# Pianoshield.net
KiCad netlist of a schematic drawn in Altium Designer
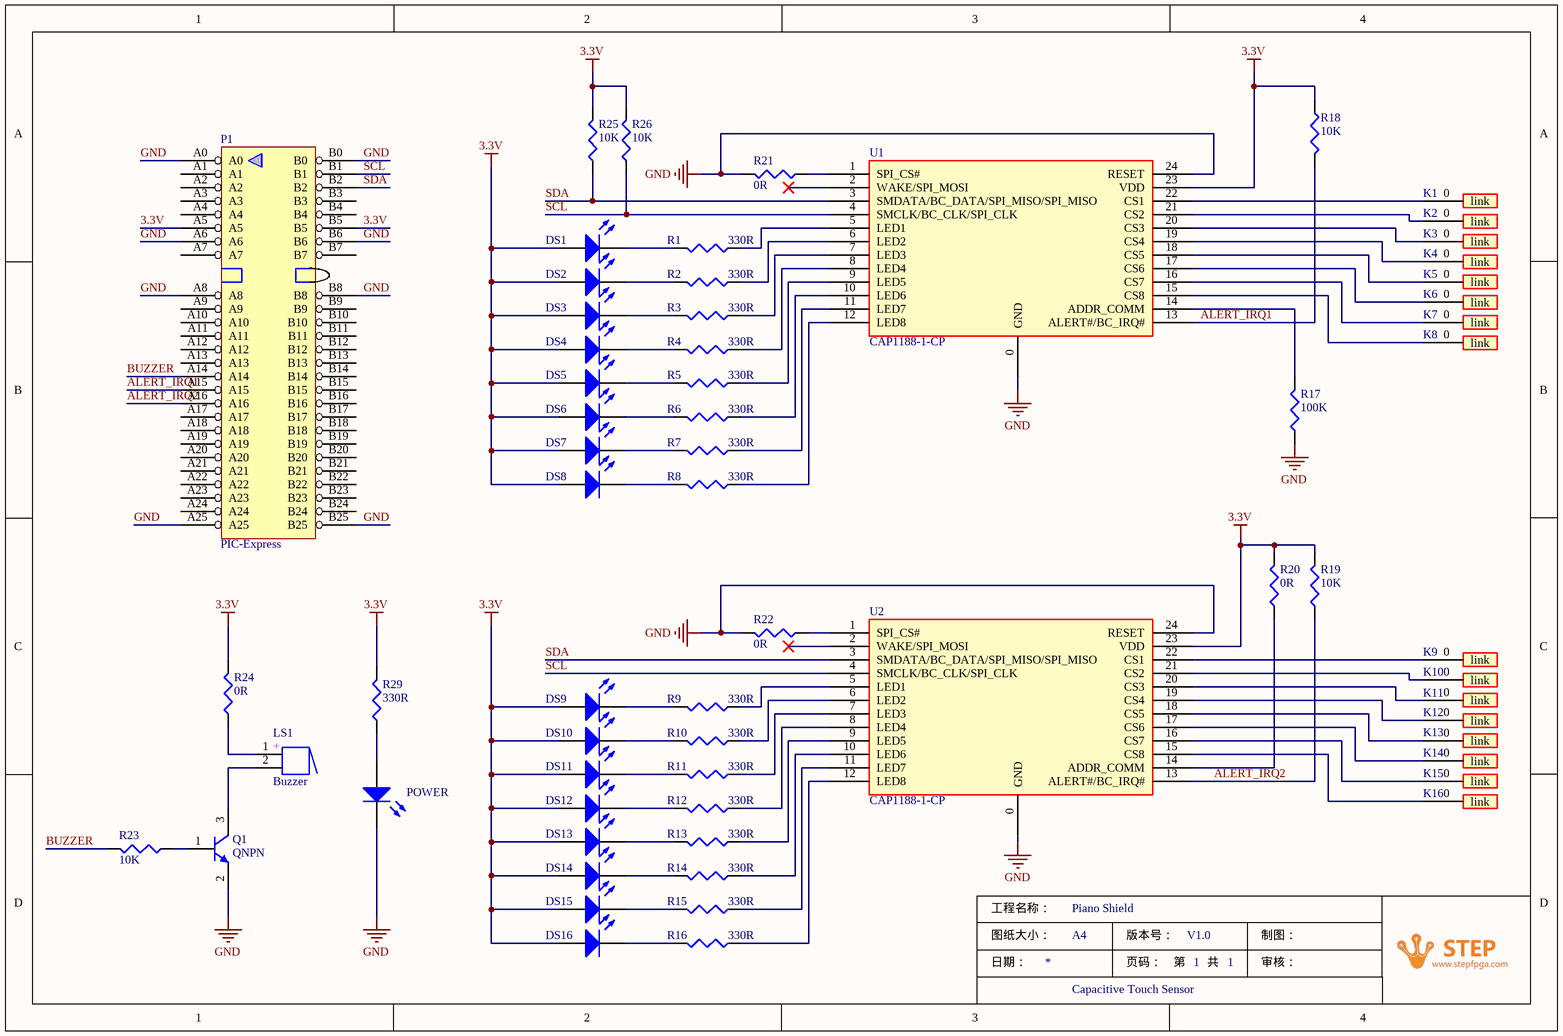
[diagram p0: Pianoshield.SchDoc]

(export (version "E")
  (design (tool "Eeschema 10.0.6"))
  (components
    (comp (ref "DS1")
      (value "Blue")
      (footprint "LED0603")
      (description "贴片LED，0603")
      (fields (field (name "PUBLISHER") "Altium Limited"))
      (libsource (lib "战舰STM32开发板底板封装库") (part "LED2"))
    )
    (comp (ref "DS2")
      (value "Blue")
      (footprint "LED0603")
      (description "贴片LED，0603")
      (fields (field (name "PUBLISHER") "Altium Limited"))
      (libsource (lib "战舰STM32开发板底板封装库") (part "LED2"))
    )
    (comp (ref "DS3")
      (value "Blue")
      (footprint "LED0603")
      (description "贴片LED，0603")
      (fields (field (name "PUBLISHER") "Altium Limited"))
      (libsource (lib "战舰STM32开发板底板封装库") (part "LED2"))
    )
    (comp (ref "DS4")
      (value "Blue")
      (footprint "LED0603")
      (description "贴片LED，0603")
      (fields (field (name "PUBLISHER") "Altium Limited"))
      (libsource (lib "战舰STM32开发板底板封装库") (part "LED2"))
    )
    (comp (ref "DS5")
      (value "Blue")
      (footprint "LED0603")
      (description "贴片LED，0603")
      (fields (field (name "PUBLISHER") "Altium Limited"))
      (libsource (lib "战舰STM32开发板底板封装库") (part "LED2"))
    )
    (comp (ref "DS6")
      (value "Blue")
      (footprint "LED0603")
      (description "贴片LED，0603")
      (fields (field (name "PUBLISHER") "Altium Limited"))
      (libsource (lib "战舰STM32开发板底板封装库") (part "LED2"))
    )
    (comp (ref "DS7")
      (value "Blue")
      (footprint "LED0603")
      (description "贴片LED，0603")
      (fields (field (name "PUBLISHER") "Altium Limited"))
      (libsource (lib "战舰STM32开发板底板封装库") (part "LED2"))
    )
    (comp (ref "DS8")
      (value "Blue")
      (footprint "LED0603")
      (description "贴片LED，0603")
      (fields (field (name "PUBLISHER") "Altium Limited"))
      (libsource (lib "战舰STM32开发板底板封装库") (part "LED2"))
    )
    (comp (ref "DS9")
      (value "Blue")
      (footprint "LED0603")
      (description "贴片LED，0603")
      (fields (field (name "PUBLISHER") "Altium Limited"))
      (libsource (lib "战舰STM32开发板底板封装库") (part "LED2"))
    )
    (comp (ref "DS10")
      (value "Blue")
      (footprint "LED0603")
      (description "贴片LED，0603")
      (fields (field (name "PUBLISHER") "Altium Limited"))
      (libsource (lib "战舰STM32开发板底板封装库") (part "LED2"))
    )
    (comp (ref "DS11")
      (value "Blue")
      (footprint "LED0603")
      (description "贴片LED，0603")
      (fields (field (name "PUBLISHER") "Altium Limited"))
      (libsource (lib "战舰STM32开发板底板封装库") (part "LED2"))
    )
    (comp (ref "DS12")
      (value "Blue")
      (footprint "LED0603")
      (description "贴片LED，0603")
      (fields (field (name "PUBLISHER") "Altium Limited"))
      (libsource (lib "战舰STM32开发板底板封装库") (part "LED2"))
    )
    (comp (ref "DS13")
      (value "Blue")
      (footprint "LED0603")
      (description "贴片LED，0603")
      (fields (field (name "PUBLISHER") "Altium Limited"))
      (libsource (lib "战舰STM32开发板底板封装库") (part "LED2"))
    )
    (comp (ref "DS14")
      (value "Blue")
      (footprint "LED0603")
      (description "贴片LED，0603")
      (fields (field (name "PUBLISHER") "Altium Limited"))
      (libsource (lib "战舰STM32开发板底板封装库") (part "LED2"))
    )
    (comp (ref "DS15")
      (value "Blue")
      (footprint "LED0603")
      (description "贴片LED，0603")
      (fields (field (name "PUBLISHER") "Altium Limited"))
      (libsource (lib "战舰STM32开发板底板封装库") (part "LED2"))
    )
    (comp (ref "DS16")
      (value "Blue")
      (footprint "LED0603")
      (description "贴片LED，0603")
      (fields (field (name "PUBLISHER") "Altium Limited"))
      (libsource (lib "战舰STM32开发板底板封装库") (part "LED2"))
    )
    (comp (ref "K1")
      (value "Keypad_1")
      (footprint "触摸按键5mm*7mm")
      (libsource (lib "CAP1188") (part "Keypad_1"))
    )
    (comp (ref "K2")
      (value "Keypad_1")
      (footprint "触摸按键5mm*7mm")
      (libsource (lib "CAP1188") (part "Keypad_1"))
    )
    (comp (ref "K3")
      (value "Keypad_1")
      (footprint "触摸按键5mm*7mm")
      (libsource (lib "CAP1188") (part "Keypad_1"))
    )
    (comp (ref "K4")
      (value "Keypad_1")
      (footprint "触摸按键5mm*7mm")
      (libsource (lib "CAP1188") (part "Keypad_1"))
    )
    (comp (ref "K5")
      (value "Keypad_1")
      (footprint "触摸按键5mm*7mm")
      (libsource (lib "CAP1188") (part "Keypad_1"))
    )
    (comp (ref "K6")
      (value "Keypad_1")
      (footprint "触摸按键5mm*7mm")
      (libsource (lib "CAP1188") (part "Keypad_1"))
    )
    (comp (ref "K7")
      (value "Keypad_1")
      (footprint "触摸按键5mm*7mm")
      (libsource (lib "CAP1188") (part "Keypad_1"))
    )
    (comp (ref "K8")
      (value "Keypad_1")
      (footprint "触摸按键5mm*7mm")
      (libsource (lib "CAP1188") (part "Keypad_1"))
    )
    (comp (ref "K9")
      (value "Keypad_1")
      (footprint "触摸按键5mm*7mm")
      (libsource (lib "CAP1188") (part "Keypad_1"))
    )
    (comp (ref "K10")
      (value "Keypad_1")
      (footprint "触摸按键5mm*7mm")
      (libsource (lib "CAP1188") (part "Keypad_1"))
    )
    (comp (ref "K11")
      (value "Keypad_1")
      (footprint "触摸按键5mm*7mm")
      (libsource (lib "CAP1188") (part "Keypad_1"))
    )
    (comp (ref "K12")
      (value "Keypad_1")
      (footprint "触摸按键5mm*7mm")
      (libsource (lib "CAP1188") (part "Keypad_1"))
    )
    (comp (ref "K13")
      (value "Keypad_1")
      (footprint "触摸按键5mm*7mm")
      (libsource (lib "CAP1188") (part "Keypad_1"))
    )
    (comp (ref "K14")
      (value "Keypad_1")
      (footprint "触摸按键5mm*7mm")
      (libsource (lib "CAP1188") (part "Keypad_1"))
    )
    (comp (ref "K15")
      (value "Keypad_1")
      (footprint "触摸按键5mm*7mm")
      (libsource (lib "CAP1188") (part "Keypad_1"))
    )
    (comp (ref "K16")
      (value "Keypad_1")
      (footprint "触摸按键5mm*7mm")
      (libsource (lib "CAP1188") (part "Keypad_1"))
    )
    (comp (ref "LS1")
      (value "Buzzer")
      (footprint "BEEPER")
      (description "Magnetic Transducer Buzzer")
      (fields (field (name "PUBLISHER") "Altium Limited"))
      (libsource (lib "step") (part "Buzzer"))
    )
    (comp (ref "P1") (value "PIC-Express") (footprint "PICE-M") (libsource (lib "step") (part "PIC-Express")))
    (comp (ref "POWER")
      (value "Green")
      (footprint "LED0603")
      (description "贴片LED，0603")
      (fields (field (name "PUBLISHER") "Altium Limited"))
      (libsource (lib "战舰STM32开发板底板封装库") (part "LED2"))
    )
    (comp (ref "Q1")
      (value "QNPN")
      (footprint "SOT-23-3")
      (description "NPN Bipolar Transistor")
      (fields (field (name "PUBLISHER") "Altium Limited"))
      (libsource (lib "Miscellaneous Devices") (part "QNPN"))
    )
    (comp (ref "R1")
      (value "330R")
      (footprint "R0201")
      (description "Resistor")
      (fields (field (name "PUBLISHER") "Altium Limited"))
      (libsource (lib "step") (part "Res"))
    )
    (comp (ref "R2")
      (value "330R")
      (footprint "R0201")
      (description "Resistor")
      (fields (field (name "PUBLISHER") "Altium Limited"))
      (libsource (lib "step") (part "Res"))
    )
    (comp (ref "R3")
      (value "330R")
      (footprint "R0201")
      (description "Resistor")
      (fields (field (name "PUBLISHER") "Altium Limited"))
      (libsource (lib "step") (part "Res"))
    )
    (comp (ref "R4")
      (value "330R")
      (footprint "R0201")
      (description "Resistor")
      (fields (field (name "PUBLISHER") "Altium Limited"))
      (libsource (lib "step") (part "Res"))
    )
    (comp (ref "R5")
      (value "330R")
      (footprint "R0201")
      (description "Resistor")
      (fields (field (name "PUBLISHER") "Altium Limited"))
      (libsource (lib "step") (part "Res"))
    )
    (comp (ref "R6")
      (value "330R")
      (footprint "R0201")
      (description "Resistor")
      (fields (field (name "PUBLISHER") "Altium Limited"))
      (libsource (lib "step") (part "Res"))
    )
    (comp (ref "R7")
      (value "330R")
      (footprint "R0201")
      (description "Resistor")
      (fields (field (name "PUBLISHER") "Altium Limited"))
      (libsource (lib "step") (part "Res"))
    )
    (comp (ref "R8")
      (value "330R")
      (footprint "R0201")
      (description "Resistor")
      (fields (field (name "PUBLISHER") "Altium Limited"))
      (libsource (lib "step") (part "Res"))
    )
    (comp (ref "R9")
      (value "330R")
      (footprint "R0201")
      (description "Resistor")
      (fields (field (name "PUBLISHER") "Altium Limited"))
      (libsource (lib "step") (part "Res"))
    )
    (comp (ref "R10")
      (value "330R")
      (footprint "R0201")
      (description "Resistor")
      (fields (field (name "PUBLISHER") "Altium Limited"))
      (libsource (lib "step") (part "Res"))
    )
    (comp (ref "R11")
      (value "330R")
      (footprint "R0201")
      (description "Resistor")
      (fields (field (name "PUBLISHER") "Altium Limited"))
      (libsource (lib "step") (part "Res"))
    )
    (comp (ref "R12")
      (value "330R")
      (footprint "R0201")
      (description "Resistor")
      (fields (field (name "PUBLISHER") "Altium Limited"))
      (libsource (lib "step") (part "Res"))
    )
    (comp (ref "R13")
      (value "330R")
      (footprint "R0201")
      (description "Resistor")
      (fields (field (name "PUBLISHER") "Altium Limited"))
      (libsource (lib "step") (part "Res"))
    )
    (comp (ref "R14")
      (value "330R")
      (footprint "R0201")
      (description "Resistor")
      (fields (field (name "PUBLISHER") "Altium Limited"))
      (libsource (lib "step") (part "Res"))
    )
    (comp (ref "R15")
      (value "330R")
      (footprint "R0201")
      (description "Resistor")
      (fields (field (name "PUBLISHER") "Altium Limited"))
      (libsource (lib "step") (part "Res"))
    )
    (comp (ref "R16")
      (value "330R")
      (footprint "R0201")
      (description "Resistor")
      (fields (field (name "PUBLISHER") "Altium Limited"))
      (libsource (lib "step") (part "Res"))
    )
    (comp (ref "R17")
      (value "100K")
      (footprint "R0201")
      (description "Resistor")
      (fields (field (name "PUBLISHER") "Altium Limited"))
      (libsource (lib "step") (part "Res"))
    )
    (comp (ref "R18")
      (value "10K")
      (footprint "R0201")
      (description "Resistor")
      (fields (field (name "PUBLISHER") "Altium Limited"))
      (libsource (lib "step") (part "Res"))
    )
    (comp (ref "R19")
      (value "10K")
      (footprint "R0201")
      (description "Resistor")
      (fields (field (name "PUBLISHER") "Altium Limited"))
      (libsource (lib "step") (part "Res"))
    )
    (comp (ref "R20")
      (value "0R")
      (footprint "R0201")
      (description "Resistor")
      (fields (field (name "PUBLISHER") "Altium Limited"))
      (libsource (lib "step") (part "Res"))
    )
    (comp (ref "R21")
      (value "0R")
      (footprint "R0201")
      (description "Resistor")
      (fields (field (name "PUBLISHER") "Altium Limited"))
      (libsource (lib "step") (part "Res"))
    )
    (comp (ref "R22")
      (value "0R")
      (footprint "R0201")
      (description "Resistor")
      (fields (field (name "PUBLISHER") "Altium Limited"))
      (libsource (lib "step") (part "Res"))
    )
    (comp (ref "R23")
      (value "10K")
      (footprint "R0201")
      (description "Resistor")
      (fields (field (name "PUBLISHER") "Altium Limited"))
      (libsource (lib "step") (part "Res"))
    )
    (comp (ref "R24")
      (value "0R")
      (footprint "R0201")
      (description "Resistor")
      (fields (field (name "PUBLISHER") "Altium Limited"))
      (libsource (lib "step") (part "Res"))
    )
    (comp (ref "R25")
      (value "10K")
      (footprint "R0201")
      (description "Resistor")
      (fields (field (name "PUBLISHER") "Altium Limited"))
      (libsource (lib "step") (part "Res"))
    )
    (comp (ref "R26")
      (value "10K")
      (footprint "R0201")
      (description "Resistor")
      (fields (field (name "PUBLISHER") "Altium Limited"))
      (libsource (lib "step") (part "Res"))
    )
    (comp (ref "R29")
      (value "330R")
      (footprint "R0201")
      (description "Resistor")
      (fields (field (name "PUBLISHER") "Altium Limited"))
      (libsource (lib "step") (part "Res"))
    )
    (comp (ref "U1")
      (value "CAP1188-1-CP")
      (footprint "战舰STM32开发板底板封装库:QFN24")
      (description "8通道电容式触摸传感，QFN24")
      (libsource (lib "CAP1188") (part "CAP1188"))
    )
    (comp (ref "U2")
      (value "CAP1188-1-CP")
      (footprint "战舰STM32开发板底板封装库:QFN24")
      (description "8通道电容式触摸传感，QFN24")
      (libsource (lib "CAP1188") (part "CAP1188"))
    )
  )
  (nets
    (net (code "1") (name "/ALERT_IRQ1") (class "Default")
      (node (ref "P1") (pin "A15") (pinfunction "A15_A15") (pintype "passive"))
      (node (ref "R18") (pin "2") (pinfunction "2_2") (pintype "passive"))
      (node (ref "U1") (pin "13") (pinfunction "ALERT#/BC_IRQ#_13") (pintype "passive"))
    )
    (net (code "2") (name "/ALERT_IRQ2") (class "Default")
      (node (ref "P1") (pin "A16") (pinfunction "A16_A16") (pintype "passive"))
      (node (ref "R19") (pin "1") (pinfunction "1_1") (pintype "passive"))
      (node (ref "U2") (pin "13") (pinfunction "ALERT#/BC_IRQ#_13") (pintype "passive"))
    )
    (net (code "3") (name "/BUZZER") (class "Default")
      (node (ref "P1") (pin "A14") (pinfunction "A14_A14") (pintype "passive"))
      (node (ref "R23") (pin "2") (pinfunction "2_2") (pintype "passive"))
    )
    (net (code "4") (name "/SCL") (class "Default")
      (node (ref "P1") (pin "B1") (pinfunction "B1_B1") (pintype "passive"))
      (node (ref "R26") (pin "1") (pinfunction "1_1") (pintype "passive"))
      (node (ref "U1") (pin "4") (pinfunction "SMCLK/BC_CLK/SPI_CLK_4") (pintype "passive"))
      (node (ref "U2") (pin "4") (pinfunction "SMCLK/BC_CLK/SPI_CLK_4") (pintype "passive"))
    )
    (net (code "5") (name "/SDA") (class "Default")
      (node (ref "P1") (pin "B2") (pinfunction "B2_B2") (pintype "passive"))
      (node (ref "R25") (pin "1") (pinfunction "1_1") (pintype "passive"))
      (node (ref "U1") (pin "3") (pinfunction "SMDATA/BC_DATA/SPI_MISO/SPI_MISO_3") (pintype "passive"))
      (node (ref "U2") (pin "3") (pinfunction "SMDATA/BC_DATA/SPI_MISO/SPI_MISO_3") (pintype "passive"))
    )
    (net (code "6") (name "3.3V") (class "Default")
      (node (ref "DS1") (pin "1") (pinfunction "A_1") (pintype "passive"))
      (node (ref "DS10") (pin "1") (pinfunction "A_1") (pintype "passive"))
      (node (ref "DS11") (pin "1") (pinfunction "A_1") (pintype "passive"))
      (node (ref "DS12") (pin "1") (pinfunction "A_1") (pintype "passive"))
      (node (ref "DS13") (pin "1") (pinfunction "A_1") (pintype "passive"))
      (node (ref "DS14") (pin "1") (pinfunction "A_1") (pintype "passive"))
      (node (ref "DS15") (pin "1") (pinfunction "A_1") (pintype "passive"))
      (node (ref "DS16") (pin "1") (pinfunction "A_1") (pintype "passive"))
      (node (ref "DS2") (pin "1") (pinfunction "A_1") (pintype "passive"))
      (node (ref "DS3") (pin "1") (pinfunction "A_1") (pintype "passive"))
      (node (ref "DS4") (pin "1") (pinfunction "A_1") (pintype "passive"))
      (node (ref "DS5") (pin "1") (pinfunction "A_1") (pintype "passive"))
      (node (ref "DS6") (pin "1") (pinfunction "A_1") (pintype "passive"))
      (node (ref "DS7") (pin "1") (pinfunction "A_1") (pintype "passive"))
      (node (ref "DS8") (pin "1") (pinfunction "A_1") (pintype "passive"))
      (node (ref "DS9") (pin "1") (pinfunction "A_1") (pintype "passive"))
      (node (ref "P1") (pin "A5") (pinfunction "A5_A5") (pintype "passive"))
      (node (ref "P1") (pin "B5") (pinfunction "B5_B5") (pintype "passive"))
      (node (ref "R18") (pin "1") (pinfunction "1_1") (pintype "passive"))
      (node (ref "R19") (pin "2") (pinfunction "2_2") (pintype "passive"))
      (node (ref "R20") (pin "2") (pinfunction "2_2") (pintype "passive"))
      (node (ref "R24") (pin "2") (pinfunction "2_2") (pintype "passive"))
      (node (ref "R25") (pin "2") (pinfunction "2_2") (pintype "passive"))
      (node (ref "R26") (pin "2") (pinfunction "2_2") (pintype "passive"))
      (node (ref "R29") (pin "2") (pinfunction "2_2") (pintype "passive"))
      (node (ref "U1") (pin "23") (pinfunction "VDD_23") (pintype "passive"))
      (node (ref "U2") (pin "23") (pinfunction "VDD_23") (pintype "passive"))
    )
    (net (code "7") (name "GND") (class "Default")
      (node (ref "P1") (pin "A0") (pinfunction "A0_A0") (pintype "passive"))
      (node (ref "P1") (pin "A25") (pinfunction "A25_A25") (pintype "passive"))
      (node (ref "P1") (pin "A6") (pinfunction "A6_A6") (pintype "passive"))
      (node (ref "P1") (pin "A8") (pinfunction "A8_A8") (pintype "passive"))
      (node (ref "P1") (pin "B0") (pinfunction "B0_B0") (pintype "passive"))
      (node (ref "P1") (pin "B25") (pinfunction "B25_B25") (pintype "passive"))
      (node (ref "P1") (pin "B6") (pinfunction "B6_B6") (pintype "passive"))
      (node (ref "P1") (pin "B8") (pinfunction "B8_B8") (pintype "passive"))
      (node (ref "POWER") (pin "2") (pinfunction "K_2") (pintype "passive"))
      (node (ref "Q1") (pin "2") (pinfunction "E_2") (pintype "passive"))
      (node (ref "R17") (pin "1") (pinfunction "1_1") (pintype "passive"))
      (node (ref "R21") (pin "2") (pinfunction "2_2") (pintype "passive"))
      (node (ref "R22") (pin "2") (pinfunction "2_2") (pintype "passive"))
      (node (ref "U1") (pin "0") (pinfunction "GND_0") (pintype "passive"))
      (node (ref "U1") (pin "24") (pinfunction "RESET_24") (pintype "passive"))
      (node (ref "U2") (pin "0") (pinfunction "GND_0") (pintype "passive"))
      (node (ref "U2") (pin "24") (pinfunction "RESET_24") (pintype "passive"))
    )
    (net (code "8") (name "Net-(DS1-K)") (class "Default")
      (node (ref "DS1") (pin "2") (pinfunction "K_2") (pintype "passive"))
      (node (ref "R1") (pin "2") (pinfunction "2_2") (pintype "passive"))
    )
    (net (code "9") (name "Net-(DS2-K)") (class "Default")
      (node (ref "DS2") (pin "2") (pinfunction "K_2") (pintype "passive"))
      (node (ref "R2") (pin "2") (pinfunction "2_2") (pintype "passive"))
    )
    (net (code "10") (name "Net-(DS3-K)") (class "Default")
      (node (ref "DS3") (pin "2") (pinfunction "K_2") (pintype "passive"))
      (node (ref "R3") (pin "2") (pinfunction "2_2") (pintype "passive"))
    )
    (net (code "11") (name "Net-(DS4-K)") (class "Default")
      (node (ref "DS4") (pin "2") (pinfunction "K_2") (pintype "passive"))
      (node (ref "R4") (pin "2") (pinfunction "2_2") (pintype "passive"))
    )
    (net (code "12") (name "Net-(DS5-K)") (class "Default")
      (node (ref "DS5") (pin "2") (pinfunction "K_2") (pintype "passive"))
      (node (ref "R5") (pin "2") (pinfunction "2_2") (pintype "passive"))
    )
    (net (code "13") (name "Net-(DS6-K)") (class "Default")
      (node (ref "DS6") (pin "2") (pinfunction "K_2") (pintype "passive"))
      (node (ref "R6") (pin "2") (pinfunction "2_2") (pintype "passive"))
    )
    (net (code "14") (name "Net-(DS7-K)") (class "Default")
      (node (ref "DS7") (pin "2") (pinfunction "K_2") (pintype "passive"))
      (node (ref "R7") (pin "2") (pinfunction "2_2") (pintype "passive"))
    )
    (net (code "15") (name "Net-(DS8-K)") (class "Default")
      (node (ref "DS8") (pin "2") (pinfunction "K_2") (pintype "passive"))
      (node (ref "R8") (pin "2") (pinfunction "2_2") (pintype "passive"))
    )
    (net (code "16") (name "Net-(DS9-K)") (class "Default")
      (node (ref "DS9") (pin "2") (pinfunction "K_2") (pintype "passive"))
      (node (ref "R9") (pin "2") (pinfunction "2_2") (pintype "passive"))
    )
    (net (code "17") (name "Net-(DS10-K)") (class "Default")
      (node (ref "DS10") (pin "2") (pinfunction "K_2") (pintype "passive"))
      (node (ref "R10") (pin "2") (pinfunction "2_2") (pintype "passive"))
    )
    (net (code "18") (name "Net-(DS11-K)") (class "Default")
      (node (ref "DS11") (pin "2") (pinfunction "K_2") (pintype "passive"))
      (node (ref "R11") (pin "2") (pinfunction "2_2") (pintype "passive"))
    )
    (net (code "19") (name "Net-(DS12-K)") (class "Default")
      (node (ref "DS12") (pin "2") (pinfunction "K_2") (pintype "passive"))
      (node (ref "R12") (pin "2") (pinfunction "2_2") (pintype "passive"))
    )
    (net (code "20") (name "Net-(DS13-K)") (class "Default")
      (node (ref "DS13") (pin "2") (pinfunction "K_2") (pintype "passive"))
      (node (ref "R13") (pin "2") (pinfunction "2_2") (pintype "passive"))
    )
    (net (code "21") (name "Net-(DS14-K)") (class "Default")
      (node (ref "DS14") (pin "2") (pinfunction "K_2") (pintype "passive"))
      (node (ref "R14") (pin "2") (pinfunction "2_2") (pintype "passive"))
    )
    (net (code "22") (name "Net-(DS15-K)") (class "Default")
      (node (ref "DS15") (pin "2") (pinfunction "K_2") (pintype "passive"))
      (node (ref "R15") (pin "2") (pinfunction "2_2") (pintype "passive"))
    )
    (net (code "23") (name "Net-(DS16-K)") (class "Default")
      (node (ref "DS16") (pin "2") (pinfunction "K_2") (pintype "passive"))
      (node (ref "R16") (pin "2") (pinfunction "2_2") (pintype "passive"))
    )
    (net (code "24") (name "Net-(K1-link)") (class "Default")
      (node (ref "K1") (pin "0") (pinfunction "link_0") (pintype "passive"))
      (node (ref "U1") (pin "22") (pinfunction "CS1_22") (pintype "passive"))
    )
    (net (code "25") (name "Net-(K2-link)") (class "Default")
      (node (ref "K2") (pin "0") (pinfunction "link_0") (pintype "passive"))
      (node (ref "U1") (pin "21") (pinfunction "CS2_21") (pintype "passive"))
    )
    (net (code "26") (name "Net-(K3-link)") (class "Default")
      (node (ref "K3") (pin "0") (pinfunction "link_0") (pintype "passive"))
      (node (ref "U1") (pin "20") (pinfunction "CS3_20") (pintype "passive"))
    )
    (net (code "27") (name "Net-(K4-link)") (class "Default")
      (node (ref "K4") (pin "0") (pinfunction "link_0") (pintype "passive"))
      (node (ref "U1") (pin "19") (pinfunction "CS4_19") (pintype "passive"))
    )
    (net (code "28") (name "Net-(K5-link)") (class "Default")
      (node (ref "K5") (pin "0") (pinfunction "link_0") (pintype "passive"))
      (node (ref "U1") (pin "18") (pinfunction "CS5_18") (pintype "passive"))
    )
    (net (code "29") (name "Net-(K6-link)") (class "Default")
      (node (ref "K6") (pin "0") (pinfunction "link_0") (pintype "passive"))
      (node (ref "U1") (pin "17") (pinfunction "CS6_17") (pintype "passive"))
    )
    (net (code "30") (name "Net-(K7-link)") (class "Default")
      (node (ref "K7") (pin "0") (pinfunction "link_0") (pintype "passive"))
      (node (ref "U1") (pin "16") (pinfunction "CS7_16") (pintype "passive"))
    )
    (net (code "31") (name "Net-(K8-link)") (class "Default")
      (node (ref "K8") (pin "0") (pinfunction "link_0") (pintype "passive"))
      (node (ref "U1") (pin "15") (pinfunction "CS8_15") (pintype "passive"))
    )
    (net (code "32") (name "Net-(K9-link)") (class "Default")
      (node (ref "K9") (pin "0") (pinfunction "link_0") (pintype "passive"))
      (node (ref "U2") (pin "22") (pinfunction "CS1_22") (pintype "passive"))
    )
    (net (code "33") (name "Net-(K10-link)") (class "Default")
      (node (ref "K10") (pin "0") (pinfunction "link_0") (pintype "passive"))
      (node (ref "U2") (pin "21") (pinfunction "CS2_21") (pintype "passive"))
    )
    (net (code "34") (name "Net-(K11-link)") (class "Default")
      (node (ref "K11") (pin "0") (pinfunction "link_0") (pintype "passive"))
      (node (ref "U2") (pin "20") (pinfunction "CS3_20") (pintype "passive"))
    )
    (net (code "35") (name "Net-(K12-link)") (class "Default")
      (node (ref "K12") (pin "0") (pinfunction "link_0") (pintype "passive"))
      (node (ref "U2") (pin "19") (pinfunction "CS4_19") (pintype "passive"))
    )
    (net (code "36") (name "Net-(K13-link)") (class "Default")
      (node (ref "K13") (pin "0") (pinfunction "link_0") (pintype "passive"))
      (node (ref "U2") (pin "18") (pinfunction "CS5_18") (pintype "passive"))
    )
    (net (code "37") (name "Net-(K14-link)") (class "Default")
      (node (ref "K14") (pin "0") (pinfunction "link_0") (pintype "passive"))
      (node (ref "U2") (pin "17") (pinfunction "CS6_17") (pintype "passive"))
    )
    (net (code "38") (name "Net-(K15-link)") (class "Default")
      (node (ref "K15") (pin "0") (pinfunction "link_0") (pintype "passive"))
      (node (ref "U2") (pin "16") (pinfunction "CS7_16") (pintype "passive"))
    )
    (net (code "39") (name "Net-(K16-link)") (class "Default")
      (node (ref "K16") (pin "0") (pinfunction "link_0") (pintype "passive"))
      (node (ref "U2") (pin "15") (pinfunction "CS8_15") (pintype "passive"))
    )
    (net (code "40") (name "Net-(LS1-Pad1)") (class "Default")
      (node (ref "LS1") (pin "1") (pinfunction "1_1") (pintype "passive"))
      (node (ref "R24") (pin "1") (pinfunction "1_1") (pintype "passive"))
    )
    (net (code "41") (name "Net-(POWER-A)") (class "Default")
      (node (ref "POWER") (pin "1") (pinfunction "A_1") (pintype "passive"))
      (node (ref "R29") (pin "1") (pinfunction "1_1") (pintype "passive"))
    )
    (net (code "42") (name "Net-(Q1-B)") (class "Default")
      (node (ref "Q1") (pin "1") (pinfunction "B_1") (pintype "passive"))
      (node (ref "R23") (pin "1") (pinfunction "1_1") (pintype "passive"))
    )
    (net (code "43") (name "Net-(Q1-C)") (class "Default")
      (node (ref "LS1") (pin "2") (pinfunction "2_2") (pintype "passive"))
      (node (ref "Q1") (pin "3") (pinfunction "C_3") (pintype "passive"))
    )
    (net (code "44") (name "Net-(U1-ADDR_COMM)") (class "Default")
      (node (ref "R17") (pin "2") (pinfunction "2_2") (pintype "passive"))
      (node (ref "U1") (pin "14") (pinfunction "ADDR_COMM_14") (pintype "passive"))
    )
    (net (code "45") (name "Net-(U1-LED1)") (class "Default")
      (node (ref "R1") (pin "1") (pinfunction "1_1") (pintype "passive"))
      (node (ref "U1") (pin "5") (pinfunction "LED1_5") (pintype "passive"))
    )
    (net (code "46") (name "Net-(U1-LED2)") (class "Default")
      (node (ref "R2") (pin "1") (pinfunction "1_1") (pintype "passive"))
      (node (ref "U1") (pin "6") (pinfunction "LED2_6") (pintype "passive"))
    )
    (net (code "47") (name "Net-(U1-LED3)") (class "Default")
      (node (ref "R3") (pin "1") (pinfunction "1_1") (pintype "passive"))
      (node (ref "U1") (pin "7") (pinfunction "LED3_7") (pintype "passive"))
    )
    (net (code "48") (name "Net-(U1-LED4)") (class "Default")
      (node (ref "R4") (pin "1") (pinfunction "1_1") (pintype "passive"))
      (node (ref "U1") (pin "8") (pinfunction "LED4_8") (pintype "passive"))
    )
    (net (code "49") (name "Net-(U1-LED5)") (class "Default")
      (node (ref "R5") (pin "1") (pinfunction "1_1") (pintype "passive"))
      (node (ref "U1") (pin "9") (pinfunction "LED5_9") (pintype "passive"))
    )
    (net (code "50") (name "Net-(U1-LED6)") (class "Default")
      (node (ref "R6") (pin "1") (pinfunction "1_1") (pintype "passive"))
      (node (ref "U1") (pin "10") (pinfunction "LED6_10") (pintype "passive"))
    )
    (net (code "51") (name "Net-(U1-LED7)") (class "Default")
      (node (ref "R7") (pin "1") (pinfunction "1_1") (pintype "passive"))
      (node (ref "U1") (pin "11") (pinfunction "LED7_11") (pintype "passive"))
    )
    (net (code "52") (name "Net-(U1-LED8)") (class "Default")
      (node (ref "R8") (pin "1") (pinfunction "1_1") (pintype "passive"))
      (node (ref "U1") (pin "12") (pinfunction "LED8_12") (pintype "passive"))
    )
    (net (code "53") (name "Net-(U1-SPI_CS#)") (class "Default")
      (node (ref "R21") (pin "1") (pinfunction "1_1") (pintype "passive"))
      (node (ref "U1") (pin "1") (pinfunction "SPI_CS#_1") (pintype "passive"))
    )
    (net (code "54") (name "Net-(U2-ADDR_COMM)") (class "Default")
      (node (ref "R20") (pin "1") (pinfunction "1_1") (pintype "passive"))
      (node (ref "U2") (pin "14") (pinfunction "ADDR_COMM_14") (pintype "passive"))
    )
    (net (code "55") (name "Net-(U2-LED1)") (class "Default")
      (node (ref "R9") (pin "1") (pinfunction "1_1") (pintype "passive"))
      (node (ref "U2") (pin "5") (pinfunction "LED1_5") (pintype "passive"))
    )
    (net (code "56") (name "Net-(U2-LED2)") (class "Default")
      (node (ref "R10") (pin "1") (pinfunction "1_1") (pintype "passive"))
      (node (ref "U2") (pin "6") (pinfunction "LED2_6") (pintype "passive"))
    )
    (net (code "57") (name "Net-(U2-LED3)") (class "Default")
      (node (ref "R11") (pin "1") (pinfunction "1_1") (pintype "passive"))
      (node (ref "U2") (pin "7") (pinfunction "LED3_7") (pintype "passive"))
    )
    (net (code "58") (name "Net-(U2-LED4)") (class "Default")
      (node (ref "R12") (pin "1") (pinfunction "1_1") (pintype "passive"))
      (node (ref "U2") (pin "8") (pinfunction "LED4_8") (pintype "passive"))
    )
    (net (code "59") (name "Net-(U2-LED5)") (class "Default")
      (node (ref "R13") (pin "1") (pinfunction "1_1") (pintype "passive"))
      (node (ref "U2") (pin "9") (pinfunction "LED5_9") (pintype "passive"))
    )
    (net (code "60") (name "Net-(U2-LED6)") (class "Default")
      (node (ref "R14") (pin "1") (pinfunction "1_1") (pintype "passive"))
      (node (ref "U2") (pin "10") (pinfunction "LED6_10") (pintype "passive"))
    )
    (net (code "61") (name "Net-(U2-LED7)") (class "Default")
      (node (ref "R15") (pin "1") (pinfunction "1_1") (pintype "passive"))
      (node (ref "U2") (pin "11") (pinfunction "LED7_11") (pintype "passive"))
    )
    (net (code "62") (name "Net-(U2-LED8)") (class "Default")
      (node (ref "R16") (pin "1") (pinfunction "1_1") (pintype "passive"))
      (node (ref "U2") (pin "12") (pinfunction "LED8_12") (pintype "passive"))
    )
    (net (code "63") (name "Net-(U2-SPI_CS#)") (class "Default")
      (node (ref "R22") (pin "1") (pinfunction "1_1") (pintype "passive"))
      (node (ref "U2") (pin "1") (pinfunction "SPI_CS#_1") (pintype "passive"))
    )
    (net (code "64") (name "unconnected-(P1-PadA1)") (class "Default")
      (node (ref "P1") (pin "A1") (pinfunction "A1_A1") (pintype "passive"))
    )
    (net (code "65") (name "unconnected-(P1-PadA2)") (class "Default")
      (node (ref "P1") (pin "A2") (pinfunction "A2_A2") (pintype "passive"))
    )
    (net (code "66") (name "unconnected-(P1-PadA3)") (class "Default")
      (node (ref "P1") (pin "A3") (pinfunction "A3_A3") (pintype "passive"))
    )
    (net (code "67") (name "unconnected-(P1-PadA4)") (class "Default")
      (node (ref "P1") (pin "A4") (pinfunction "A4_A4") (pintype "passive"))
    )
    (net (code "68") (name "unconnected-(P1-PadA7)") (class "Default")
      (node (ref "P1") (pin "A7") (pinfunction "A7_A7") (pintype "passive"))
    )
    (net (code "69") (name "unconnected-(P1-PadA9)") (class "Default")
      (node (ref "P1") (pin "A9") (pinfunction "A9_A9") (pintype "passive"))
    )
    (net (code "70") (name "unconnected-(P1-PadA10)") (class "Default")
      (node (ref "P1") (pin "A10") (pinfunction "A10_A10") (pintype "passive"))
    )
    (net (code "71") (name "unconnected-(P1-PadA11)") (class "Default")
      (node (ref "P1") (pin "A11") (pinfunction "A11_A11") (pintype "passive"))
    )
    (net (code "72") (name "unconnected-(P1-PadA12)") (class "Default")
      (node (ref "P1") (pin "A12") (pinfunction "A12_A12") (pintype "passive"))
    )
    (net (code "73") (name "unconnected-(P1-PadA13)") (class "Default")
      (node (ref "P1") (pin "A13") (pinfunction "A13_A13") (pintype "passive"))
    )
    (net (code "74") (name "unconnected-(P1-PadA17)") (class "Default")
      (node (ref "P1") (pin "A17") (pinfunction "A17_A17") (pintype "passive"))
    )
    (net (code "75") (name "unconnected-(P1-PadA18)") (class "Default")
      (node (ref "P1") (pin "A18") (pinfunction "A18_A18") (pintype "passive"))
    )
    (net (code "76") (name "unconnected-(P1-PadA19)") (class "Default")
      (node (ref "P1") (pin "A19") (pinfunction "A19_A19") (pintype "passive"))
    )
    (net (code "77") (name "unconnected-(P1-PadA20)") (class "Default")
      (node (ref "P1") (pin "A20") (pinfunction "A20_A20") (pintype "passive"))
    )
    (net (code "78") (name "unconnected-(P1-PadA21)") (class "Default")
      (node (ref "P1") (pin "A21") (pinfunction "A21_A21") (pintype "passive"))
    )
    (net (code "79") (name "unconnected-(P1-PadA22)") (class "Default")
      (node (ref "P1") (pin "A22") (pinfunction "A22_A22") (pintype "passive"))
    )
    (net (code "80") (name "unconnected-(P1-PadA23)") (class "Default")
      (node (ref "P1") (pin "A23") (pinfunction "A23_A23") (pintype "passive"))
    )
    (net (code "81") (name "unconnected-(P1-PadA24)") (class "Default")
      (node (ref "P1") (pin "A24") (pinfunction "A24_A24") (pintype "passive"))
    )
    (net (code "82") (name "unconnected-(P1-PadB3)") (class "Default")
      (node (ref "P1") (pin "B3") (pinfunction "B3_B3") (pintype "passive"))
    )
    (net (code "83") (name "unconnected-(P1-PadB4)") (class "Default")
      (node (ref "P1") (pin "B4") (pinfunction "B4_B4") (pintype "passive"))
    )
    (net (code "84") (name "unconnected-(P1-PadB7)") (class "Default")
      (node (ref "P1") (pin "B7") (pinfunction "B7_B7") (pintype "passive"))
    )
    (net (code "85") (name "unconnected-(P1-PadB9)") (class "Default")
      (node (ref "P1") (pin "B9") (pinfunction "B9_B9") (pintype "passive"))
    )
    (net (code "86") (name "unconnected-(P1-PadB10)") (class "Default")
      (node (ref "P1") (pin "B10") (pinfunction "B10_B10") (pintype "passive"))
    )
    (net (code "87") (name "unconnected-(P1-PadB11)") (class "Default")
      (node (ref "P1") (pin "B11") (pinfunction "B11_B11") (pintype "passive"))
    )
    (net (code "88") (name "unconnected-(P1-PadB12)") (class "Default")
      (node (ref "P1") (pin "B12") (pinfunction "B12_B12") (pintype "passive"))
    )
    (net (code "89") (name "unconnected-(P1-PadB13)") (class "Default")
      (node (ref "P1") (pin "B13") (pinfunction "B13_B13") (pintype "passive"))
    )
    (net (code "90") (name "unconnected-(P1-PadB14)") (class "Default")
      (node (ref "P1") (pin "B14") (pinfunction "B14_B14") (pintype "passive"))
    )
    (net (code "91") (name "unconnected-(P1-PadB15)") (class "Default")
      (node (ref "P1") (pin "B15") (pinfunction "B15_B15") (pintype "passive"))
    )
    (net (code "92") (name "unconnected-(P1-PadB16)") (class "Default")
      (node (ref "P1") (pin "B16") (pinfunction "B16_B16") (pintype "passive"))
    )
    (net (code "93") (name "unconnected-(P1-PadB17)") (class "Default")
      (node (ref "P1") (pin "B17") (pinfunction "B17_B17") (pintype "passive"))
    )
    (net (code "94") (name "unconnected-(P1-PadB18)") (class "Default")
      (node (ref "P1") (pin "B18") (pinfunction "B18_B18") (pintype "passive"))
    )
    (net (code "95") (name "unconnected-(P1-PadB19)") (class "Default")
      (node (ref "P1") (pin "B19") (pinfunction "B19_B19") (pintype "passive"))
    )
    (net (code "96") (name "unconnected-(P1-PadB20)") (class "Default")
      (node (ref "P1") (pin "B20") (pinfunction "B20_B20") (pintype "passive"))
    )
    (net (code "97") (name "unconnected-(P1-PadB21)") (class "Default")
      (node (ref "P1") (pin "B21") (pinfunction "B21_B21") (pintype "passive"))
    )
    (net (code "98") (name "unconnected-(P1-PadB22)") (class "Default")
      (node (ref "P1") (pin "B22") (pinfunction "B22_B22") (pintype "passive"))
    )
    (net (code "99") (name "unconnected-(P1-PadB23)") (class "Default")
      (node (ref "P1") (pin "B23") (pinfunction "B23_B23") (pintype "passive"))
    )
    (net (code "100") (name "unconnected-(P1-PadB24)") (class "Default")
      (node (ref "P1") (pin "B24") (pinfunction "B24_B24") (pintype "passive"))
    )
    (net (code "101") (name "unconnected-(U1-WAKE{slash}SPI_MOSI-Pad2)") (class "Default")
      (node (ref "U1") (pin "2") (pinfunction "WAKE/SPI_MOSI_2") (pintype "passive+no_connect"))
    )
    (net (code "102") (name "unconnected-(U2-WAKE{slash}SPI_MOSI-Pad2)") (class "Default")
      (node (ref "U2") (pin "2") (pinfunction "WAKE/SPI_MOSI_2") (pintype "passive+no_connect"))
    )
  )
)
